# atmusic.net
KiCad netlist of a schematic drawn in Altium Designer
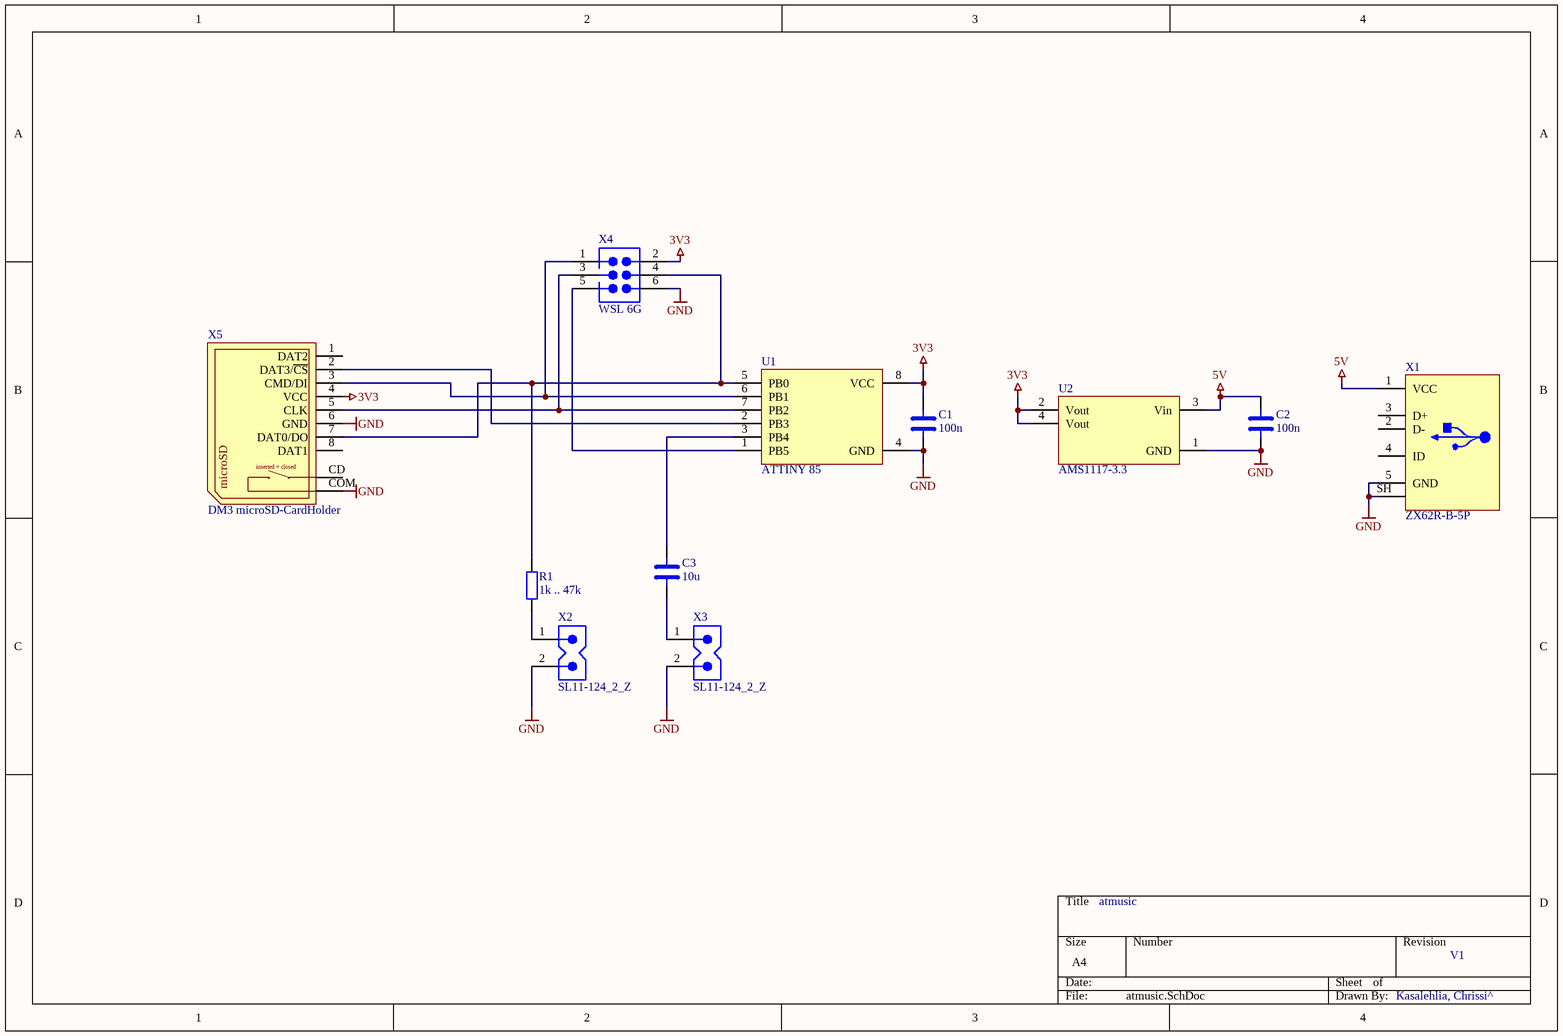
[diagram p0: atmusic.SchDoc]

(export (version "E")
  (design (tool "Eeschema 10.0.6"))
  (components
    (comp (ref "C1")
      (value "100n")
      (footprint "CAPC1608X06N")
      (description "100nF ±10% 0603 X7R Chip Capacitor, 16V")
      (fields (field (name "PART NUMBER") "X7R-G0603 100N"))
      (libsource (lib "Reichelt") (part "CAP_2_V1"))
    )
    (comp (ref "C2")
      (value "100n")
      (footprint "CAPC1608X06N")
      (description "100nF ±10% 0603 X7R Chip Capacitor, 16V")
      (fields (field (name "PART NUMBER") "X7R-G0603 100N"))
      (libsource (lib "Reichelt") (part "CAP_2_V1"))
    )
    (comp (ref "C3")
      (value "10u")
      (footprint "CAPC3216X07N")
      (description "10uF ±10% 1206 X7R Chip Capacitor, 25V")
      (fields (field (name "PART NUMBER") "X7R-G1206 10/25"))
      (libsource (lib "Reichelt") (part "CAP_2_V1"))
    )
    (comp (ref "R1")
      (value "1k .. 47k")
      (footprint "RESC1608X06N")
      (description "1% 100mW 0603 Chip Resistor E12")
      (fields (field (name "PART NUMBER") "SMD R 0603"))
      (libsource (lib "Reichelt") (part "RES_2_V1"))
    )
    (comp (ref "U1")
      (value "ATTINY 85")
      (footprint "SOIC127P800X216-8N")
      (description "8-Bit Microcontroller with 8kBytes Flash")
      (fields (field (name "PART NUMBER") "ATTINY 85-20 SU") (field (name "ERSTELLER") "cf"))
      (libsource (lib "Reichelt") (part "ATTINYxx"))
    )
    (comp (ref "U2")
      (value "AMS1117-3.3")
      (footprint "SOT230P700X180-4N")
      (description "Low cost fixed linear regulator")
      (fields (field (name "ERSTELLER") "cf"))
      (libsource (lib "Other") (part "AMS1117-3.3"))
    )
    (comp (ref "X1")
      (value "ZX62R-B-5P")
      (footprint "ZX62R-B-5P")
      (description "Micro-USB, SMT, Reverse")
      (fields (field (name "DISTRIBUTOR_1_PART_NUMBER") "2300439") (field (name "ERSTELLER") "avd"))
      (libsource (lib "Other") (part "USB_MICRO"))
    )
    (comp (ref "X2")
      (value "SL11-124_2_Z")
      (footprint "Fischer_SL11-124_2_x")
      (description "Stiftleiste THT 2 reihig Rastermaß 2,54mm")
      (fields (field (name "ERSTELLER") "gserhorn"))
      (libsource (lib "Altium_lib") (part "Fischer_SL11-124_x_x"))
    )
    (comp (ref "X3")
      (value "SL11-124_2_Z")
      (footprint "Fischer_SL11-124_2_x")
      (description "Stiftleiste THT 2 reihig Rastermaß 2,54mm")
      (fields (field (name "ERSTELLER") "gserhorn"))
      (libsource (lib "Altium_lib") (part "Fischer_SL11-124_x_x"))
    )
    (comp (ref "X4")
      (value "WSL 6G")
      (footprint "WSL_6G")
      (description "Wannenstecker, 6Pol, 2,54mm RM")
      (fields (field (name "ERSTELLER") "cf"))
      (libsource (lib "Reichelt") (part "WSL_6G"))
    )
    (comp (ref "X5")
      (value "DM3 microSD-CardHolder")
      (footprint "DM3CS-SF")
      (description "DM3-Series microSD Memory-Card Hinge Connector (Push-Pull, no election)")
      (fields (field (name "PART NUMBER") "DM3CS-SF") (field (name "ERSTELLER") "gmbaetje"))
      (libsource (lib "Altium_lib") (part "DM3CS-SF"))
    )
  )
  (nets
    (net (code "1") (name "3V3") (class "Default")
      (node (ref "C1") (pin "2") (pinfunction "2_2") (pintype "passive"))
      (node (ref "U1") (pin "8") (pinfunction "VCC_8") (pintype "passive"))
      (node (ref "U2") (pin "2") (pinfunction "Vout_2") (pintype "passive"))
      (node (ref "U2") (pin "4") (pinfunction "Vout_4") (pintype "passive"))
      (node (ref "X4") (pin "2") (pinfunction "2_2") (pintype "passive"))
      (node (ref "X5") (pin "4") (pinfunction "VCC_4") (pintype "passive"))
    )
    (net (code "2") (name "5V") (class "Default")
      (node (ref "C2") (pin "2") (pinfunction "2_2") (pintype "passive"))
      (node (ref "U2") (pin "3") (pinfunction "Vin_3") (pintype "passive"))
      (node (ref "X1") (pin "1") (pinfunction "VCC_1") (pintype "passive"))
    )
    (net (code "3") (name "GND") (class "Default")
      (node (ref "C1") (pin "1") (pinfunction "1_1") (pintype "passive"))
      (node (ref "C2") (pin "1") (pinfunction "1_1") (pintype "passive"))
      (node (ref "U1") (pin "4") (pinfunction "GND_4") (pintype "passive"))
      (node (ref "U2") (pin "1") (pinfunction "GND_1") (pintype "passive"))
      (node (ref "X1") (pin "5") (pinfunction "GND_5") (pintype "passive"))
      (node (ref "X1") (pin "SH") (pinfunction "SH_SH") (pintype "passive"))
      (node (ref "X2") (pin "2") (pinfunction "2_2") (pintype "passive"))
      (node (ref "X3") (pin "2") (pinfunction "2_2") (pintype "passive"))
      (node (ref "X4") (pin "6") (pinfunction "6_6") (pintype "passive"))
      (node (ref "X5") (pin "6") (pinfunction "GND_6") (pintype "passive"))
      (node (ref "X5") (pin "COM") (pinfunction "COM_COM") (pintype "passive"))
    )
    (net (code "4") (name "Net-(C3-Pad1)") (class "Default")
      (node (ref "C3") (pin "1") (pinfunction "1_1") (pintype "passive"))
      (node (ref "X3") (pin "1") (pinfunction "1_1") (pintype "passive"))
    )
    (net (code "5") (name "Net-(R1-Pad1)") (class "Default")
      (node (ref "R1") (pin "1") (pinfunction "1_1") (pintype "passive"))
      (node (ref "X2") (pin "1") (pinfunction "1_1") (pintype "passive"))
    )
    (net (code "6") (name "Net-(U1-PB0)") (class "Default")
      (node (ref "R1") (pin "2") (pinfunction "2_2") (pintype "passive"))
      (node (ref "U1") (pin "5") (pinfunction "PB0_5") (pintype "passive"))
      (node (ref "X4") (pin "4") (pinfunction "4_4") (pintype "passive"))
      (node (ref "X5") (pin "7") (pinfunction "DAT0/DO_7") (pintype "passive"))
    )
    (net (code "7") (name "Net-(U1-PB1)") (class "Default")
      (node (ref "U1") (pin "6") (pinfunction "PB1_6") (pintype "passive"))
      (node (ref "X4") (pin "1") (pinfunction "1_1") (pintype "passive"))
      (node (ref "X5") (pin "3") (pinfunction "CMD/DI_3") (pintype "passive"))
    )
    (net (code "8") (name "Net-(U1-PB2)") (class "Default")
      (node (ref "U1") (pin "7") (pinfunction "PB2_7") (pintype "passive"))
      (node (ref "X4") (pin "3") (pinfunction "3_3") (pintype "passive"))
      (node (ref "X5") (pin "5") (pinfunction "CLK_5") (pintype "passive"))
    )
    (net (code "9") (name "Net-(U1-PB3)") (class "Default")
      (node (ref "U1") (pin "2") (pinfunction "PB3_2") (pintype "passive"))
      (node (ref "X5") (pin "2") (pinfunction "DAT3/~{CS}_2") (pintype "passive"))
    )
    (net (code "10") (name "Net-(U1-PB4)") (class "Default")
      (node (ref "C3") (pin "2") (pinfunction "2_2") (pintype "passive"))
      (node (ref "U1") (pin "3") (pinfunction "PB4_3") (pintype "passive"))
    )
    (net (code "11") (name "Net-(U1-PB5)") (class "Default")
      (node (ref "U1") (pin "1") (pinfunction "PB5_1") (pintype "passive"))
      (node (ref "X4") (pin "5") (pinfunction "5_5") (pintype "passive"))
    )
    (net (code "12") (name "unconnected-(X1-D+-Pad3)") (class "Default")
      (node (ref "X1") (pin "3") (pinfunction "D+_3") (pintype "passive"))
    )
    (net (code "13") (name "unconnected-(X1-D--Pad2)") (class "Default")
      (node (ref "X1") (pin "2") (pinfunction "D-_2") (pintype "passive"))
    )
    (net (code "14") (name "unconnected-(X1-ID-Pad4)") (class "Default")
      (node (ref "X1") (pin "4") (pinfunction "ID_4") (pintype "passive"))
    )
    (net (code "15") (name "unconnected-(X5-DAT1-Pad8)") (class "Default")
      (node (ref "X5") (pin "8") (pinfunction "DAT1_8") (pintype "passive"))
    )
    (net (code "16") (name "unconnected-(X5-DAT2-Pad1)") (class "Default")
      (node (ref "X5") (pin "1") (pinfunction "DAT2_1") (pintype "passive"))
    )
    (net (code "17") (name "unconnected-(X5-PadCD)") (class "Default")
      (node (ref "X5") (pin "CD") (pinfunction "CD_CD") (pintype "passive"))
    )
  )
)
